# OutputDigital.net
KiCad netlist of a schematic drawn in Altium Designer
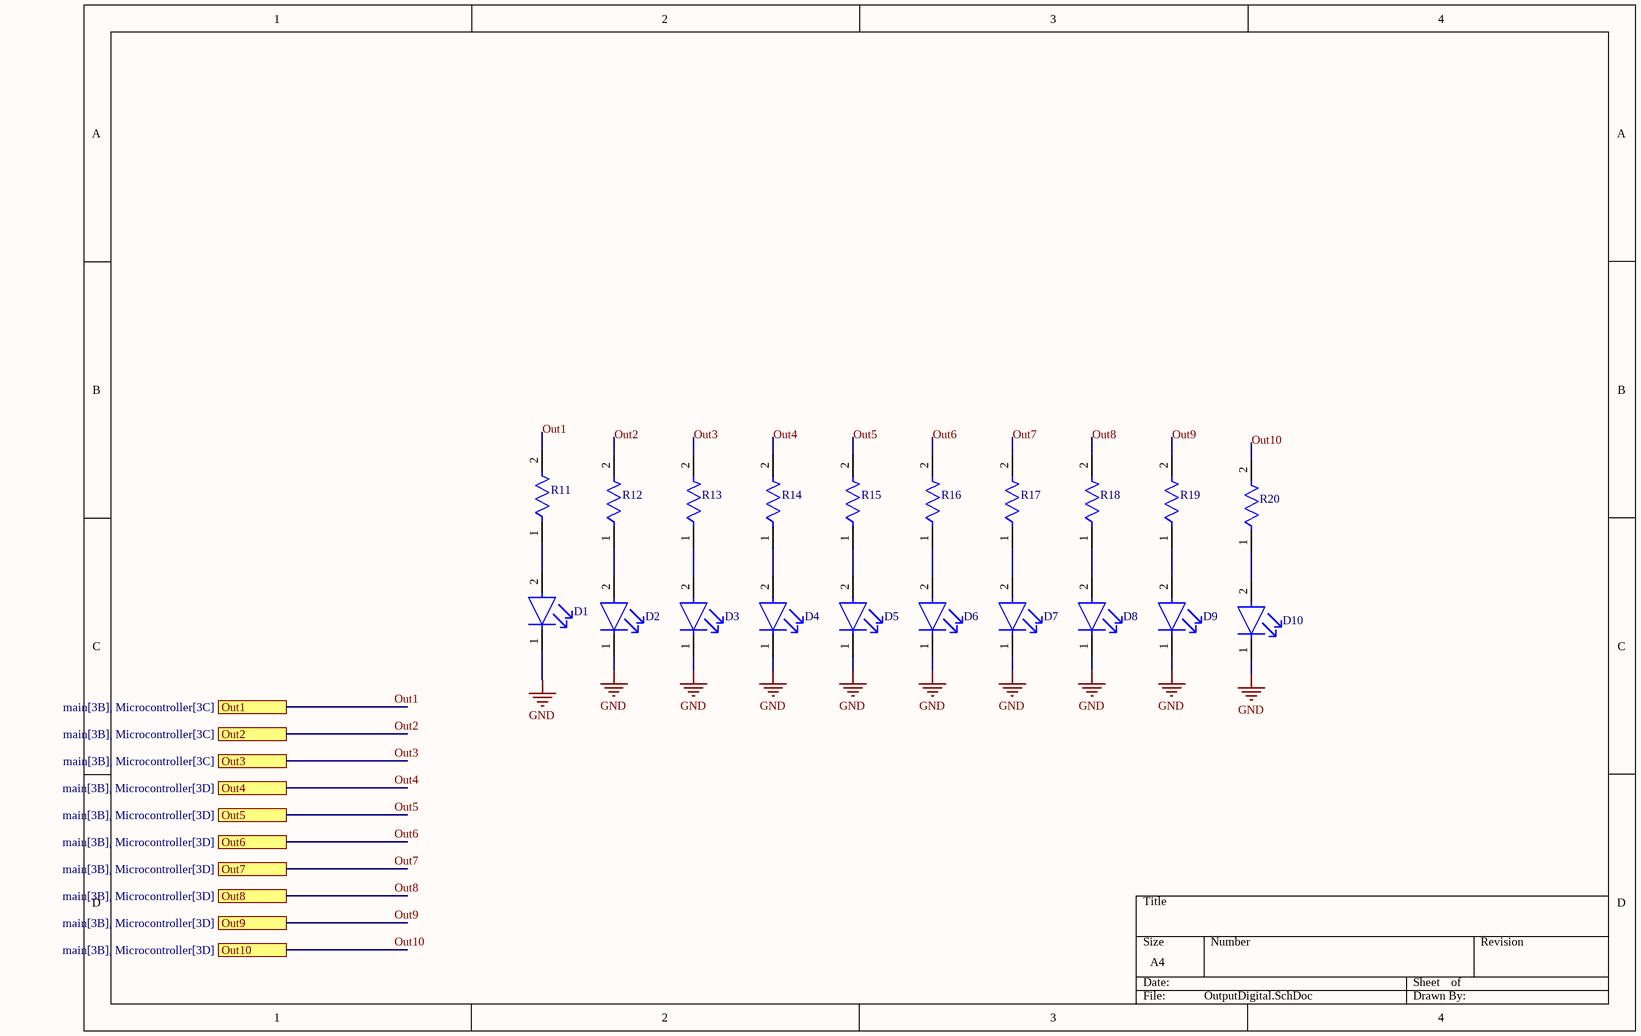
[diagram p0: OutputDigital.SchDoc]

(export (version "E")
  (design (tool "Eeschema 10.0.6"))
  (components
    (comp (ref "D1")
      (value "LTST-C230KRKT")
      (footprint "FP-LTST-C230KRKT-MFG")
      (description "LED RED CLEAR CHIP SMD")
      (libsource (lib "Ejemplo2") (part "CMP-22017-000041-1"))
    )
    (comp (ref "D2")
      (value "LTST-C230KRKT")
      (footprint "FP-LTST-C230KRKT-MFG")
      (description "LED RED CLEAR CHIP SMD")
      (libsource (lib "Ejemplo2") (part "CMP-22017-000041-1"))
    )
    (comp (ref "D3")
      (value "LTST-C230KRKT")
      (footprint "FP-LTST-C230KRKT-MFG")
      (description "LED RED CLEAR CHIP SMD")
      (libsource (lib "Ejemplo2") (part "CMP-22017-000041-1"))
    )
    (comp (ref "D4")
      (value "LTST-C230KRKT")
      (footprint "FP-LTST-C230KRKT-MFG")
      (description "LED RED CLEAR CHIP SMD")
      (libsource (lib "Ejemplo2") (part "CMP-22017-000041-1"))
    )
    (comp (ref "D5")
      (value "LTST-C230KRKT")
      (footprint "FP-LTST-C230KRKT-MFG")
      (description "LED RED CLEAR CHIP SMD")
      (libsource (lib "Ejemplo2") (part "CMP-22017-000041-1"))
    )
    (comp (ref "D6")
      (value "LTST-C230KRKT")
      (footprint "FP-LTST-C230KRKT-MFG")
      (description "LED RED CLEAR CHIP SMD")
      (libsource (lib "Ejemplo2") (part "CMP-22017-000041-1"))
    )
    (comp (ref "D7")
      (value "LTST-C230KRKT")
      (footprint "FP-LTST-C230KRKT-MFG")
      (description "LED RED CLEAR CHIP SMD")
      (libsource (lib "Ejemplo2") (part "CMP-22017-000041-1"))
    )
    (comp (ref "D8")
      (value "LTST-C230KRKT")
      (footprint "FP-LTST-C230KRKT-MFG")
      (description "LED RED CLEAR CHIP SMD")
      (libsource (lib "Ejemplo2") (part "CMP-22017-000041-1"))
    )
    (comp (ref "D9")
      (value "LTST-C230KRKT")
      (footprint "FP-LTST-C230KRKT-MFG")
      (description "LED RED CLEAR CHIP SMD")
      (libsource (lib "Ejemplo2") (part "CMP-22017-000041-1"))
    )
    (comp (ref "D10")
      (value "LTST-C230KRKT")
      (footprint "FP-LTST-C230KRKT-MFG")
      (description "LED RED CLEAR CHIP SMD")
      (libsource (lib "Ejemplo2") (part "CMP-22017-000041-1"))
    )
    (comp (ref "R11")
      (value "RT0805BRD07249RL")
      (footprint "FP-RT0805-MFG")
      (description "RES SMD 249 OHM 0.1% 1/8W 0805")
      (fields
        (field (name "OCTOPART") "https://octopart.com/rt0805brd07249rl-yageo-1410573")
        (field (name "MANUFACTURER") "Yageo")
      )
      (libsource (lib "Ejemplo2") (part "CMP-03412-035801-1"))
    )
    (comp (ref "R12")
      (value "RT0805BRD07249RL")
      (footprint "FP-RT0805-MFG")
      (description "RES SMD 249 OHM 0.1% 1/8W 0805")
      (fields
        (field (name "OCTOPART") "https://octopart.com/rt0805brd07249rl-yageo-1410573")
        (field (name "MANUFACTURER") "Yageo")
      )
      (libsource (lib "Ejemplo2") (part "CMP-03412-035801-1"))
    )
    (comp (ref "R13")
      (value "RT0805BRD07249RL")
      (footprint "FP-RT0805-MFG")
      (description "RES SMD 249 OHM 0.1% 1/8W 0805")
      (fields
        (field (name "OCTOPART") "https://octopart.com/rt0805brd07249rl-yageo-1410573")
        (field (name "MANUFACTURER") "Yageo")
      )
      (libsource (lib "Ejemplo2") (part "CMP-03412-035801-1"))
    )
    (comp (ref "R14")
      (value "RT0805BRD07249RL")
      (footprint "FP-RT0805-MFG")
      (description "RES SMD 249 OHM 0.1% 1/8W 0805")
      (fields
        (field (name "OCTOPART") "https://octopart.com/rt0805brd07249rl-yageo-1410573")
        (field (name "MANUFACTURER") "Yageo")
      )
      (libsource (lib "Ejemplo2") (part "CMP-03412-035801-1"))
    )
    (comp (ref "R15")
      (value "RT0805BRD07249RL")
      (footprint "FP-RT0805-MFG")
      (description "RES SMD 249 OHM 0.1% 1/8W 0805")
      (fields
        (field (name "OCTOPART") "https://octopart.com/rt0805brd07249rl-yageo-1410573")
        (field (name "MANUFACTURER") "Yageo")
      )
      (libsource (lib "Ejemplo2") (part "CMP-03412-035801-1"))
    )
    (comp (ref "R16")
      (value "RT0805BRD07249RL")
      (footprint "FP-RT0805-MFG")
      (description "RES SMD 249 OHM 0.1% 1/8W 0805")
      (fields
        (field (name "OCTOPART") "https://octopart.com/rt0805brd07249rl-yageo-1410573")
        (field (name "MANUFACTURER") "Yageo")
      )
      (libsource (lib "Ejemplo2") (part "CMP-03412-035801-1"))
    )
    (comp (ref "R17")
      (value "RT0805BRD07249RL")
      (footprint "FP-RT0805-MFG")
      (description "RES SMD 249 OHM 0.1% 1/8W 0805")
      (fields
        (field (name "OCTOPART") "https://octopart.com/rt0805brd07249rl-yageo-1410573")
        (field (name "MANUFACTURER") "Yageo")
      )
      (libsource (lib "Ejemplo2") (part "CMP-03412-035801-1"))
    )
    (comp (ref "R18")
      (value "RT0805BRD07249RL")
      (footprint "FP-RT0805-MFG")
      (description "RES SMD 249 OHM 0.1% 1/8W 0805")
      (fields
        (field (name "OCTOPART") "https://octopart.com/rt0805brd07249rl-yageo-1410573")
        (field (name "MANUFACTURER") "Yageo")
      )
      (libsource (lib "Ejemplo2") (part "CMP-03412-035801-1"))
    )
    (comp (ref "R19")
      (value "RT0805BRD07249RL")
      (footprint "FP-RT0805-MFG")
      (description "RES SMD 249 OHM 0.1% 1/8W 0805")
      (fields
        (field (name "OCTOPART") "https://octopart.com/rt0805brd07249rl-yageo-1410573")
        (field (name "MANUFACTURER") "Yageo")
      )
      (libsource (lib "Ejemplo2") (part "CMP-03412-035801-1"))
    )
    (comp (ref "R20")
      (value "RT0805BRD07249RL")
      (footprint "FP-RT0805-MFG")
      (description "RES SMD 249 OHM 0.1% 1/8W 0805")
      (fields
        (field (name "OCTOPART") "https://octopart.com/rt0805brd07249rl-yageo-1410573")
        (field (name "MANUFACTURER") "Yageo")
      )
      (libsource (lib "Ejemplo2") (part "CMP-03412-035801-1"))
    )
  )
  (nets
    (net (code "1") (name "/Out1") (class "Default")
      (node (ref "R11") (pin "2") (pinfunction "2_2") (pintype "passive"))
    )
    (net (code "2") (name "/Out2") (class "Default")
      (node (ref "R12") (pin "2") (pinfunction "2_2") (pintype "passive"))
    )
    (net (code "3") (name "/Out3") (class "Default")
      (node (ref "R13") (pin "2") (pinfunction "2_2") (pintype "passive"))
    )
    (net (code "4") (name "/Out4") (class "Default")
      (node (ref "R14") (pin "2") (pinfunction "2_2") (pintype "passive"))
    )
    (net (code "5") (name "/Out5") (class "Default")
      (node (ref "R15") (pin "2") (pinfunction "2_2") (pintype "passive"))
    )
    (net (code "6") (name "/Out6") (class "Default")
      (node (ref "R16") (pin "2") (pinfunction "2_2") (pintype "passive"))
    )
    (net (code "7") (name "/Out7") (class "Default")
      (node (ref "R17") (pin "2") (pinfunction "2_2") (pintype "passive"))
    )
    (net (code "8") (name "/Out8") (class "Default")
      (node (ref "R18") (pin "2") (pinfunction "2_2") (pintype "passive"))
    )
    (net (code "9") (name "/Out9") (class "Default")
      (node (ref "R19") (pin "2") (pinfunction "2_2") (pintype "passive"))
    )
    (net (code "10") (name "/Out10") (class "Default")
      (node (ref "R20") (pin "2") (pinfunction "2_2") (pintype "passive"))
    )
    (net (code "11") (name "GND") (class "Default")
      (node (ref "D1") (pin "1") (pinfunction "C_1") (pintype "passive"))
      (node (ref "D10") (pin "1") (pinfunction "C_1") (pintype "passive"))
      (node (ref "D2") (pin "1") (pinfunction "C_1") (pintype "passive"))
      (node (ref "D3") (pin "1") (pinfunction "C_1") (pintype "passive"))
      (node (ref "D4") (pin "1") (pinfunction "C_1") (pintype "passive"))
      (node (ref "D5") (pin "1") (pinfunction "C_1") (pintype "passive"))
      (node (ref "D6") (pin "1") (pinfunction "C_1") (pintype "passive"))
      (node (ref "D7") (pin "1") (pinfunction "C_1") (pintype "passive"))
      (node (ref "D8") (pin "1") (pinfunction "C_1") (pintype "passive"))
      (node (ref "D9") (pin "1") (pinfunction "C_1") (pintype "passive"))
    )
    (net (code "12") (name "Net-(D1-A)") (class "Default")
      (node (ref "D1") (pin "2") (pinfunction "A_2") (pintype "passive"))
      (node (ref "R11") (pin "1") (pinfunction "1_1") (pintype "passive"))
    )
    (net (code "13") (name "Net-(D2-A)") (class "Default")
      (node (ref "D2") (pin "2") (pinfunction "A_2") (pintype "passive"))
      (node (ref "R12") (pin "1") (pinfunction "1_1") (pintype "passive"))
    )
    (net (code "14") (name "Net-(D3-A)") (class "Default")
      (node (ref "D3") (pin "2") (pinfunction "A_2") (pintype "passive"))
      (node (ref "R13") (pin "1") (pinfunction "1_1") (pintype "passive"))
    )
    (net (code "15") (name "Net-(D4-A)") (class "Default")
      (node (ref "D4") (pin "2") (pinfunction "A_2") (pintype "passive"))
      (node (ref "R14") (pin "1") (pinfunction "1_1") (pintype "passive"))
    )
    (net (code "16") (name "Net-(D5-A)") (class "Default")
      (node (ref "D5") (pin "2") (pinfunction "A_2") (pintype "passive"))
      (node (ref "R15") (pin "1") (pinfunction "1_1") (pintype "passive"))
    )
    (net (code "17") (name "Net-(D6-A)") (class "Default")
      (node (ref "D6") (pin "2") (pinfunction "A_2") (pintype "passive"))
      (node (ref "R16") (pin "1") (pinfunction "1_1") (pintype "passive"))
    )
    (net (code "18") (name "Net-(D7-A)") (class "Default")
      (node (ref "D7") (pin "2") (pinfunction "A_2") (pintype "passive"))
      (node (ref "R17") (pin "1") (pinfunction "1_1") (pintype "passive"))
    )
    (net (code "19") (name "Net-(D8-A)") (class "Default")
      (node (ref "D8") (pin "2") (pinfunction "A_2") (pintype "passive"))
      (node (ref "R18") (pin "1") (pinfunction "1_1") (pintype "passive"))
    )
    (net (code "20") (name "Net-(D9-A)") (class "Default")
      (node (ref "D9") (pin "2") (pinfunction "A_2") (pintype "passive"))
      (node (ref "R19") (pin "1") (pinfunction "1_1") (pintype "passive"))
    )
    (net (code "21") (name "Net-(D10-A)") (class "Default")
      (node (ref "D10") (pin "2") (pinfunction "A_2") (pintype "passive"))
      (node (ref "R20") (pin "1") (pinfunction "1_1") (pintype "passive"))
    )
  )
)
